# PI_CON.net
KiCad netlist of a schematic drawn in Altium Designer
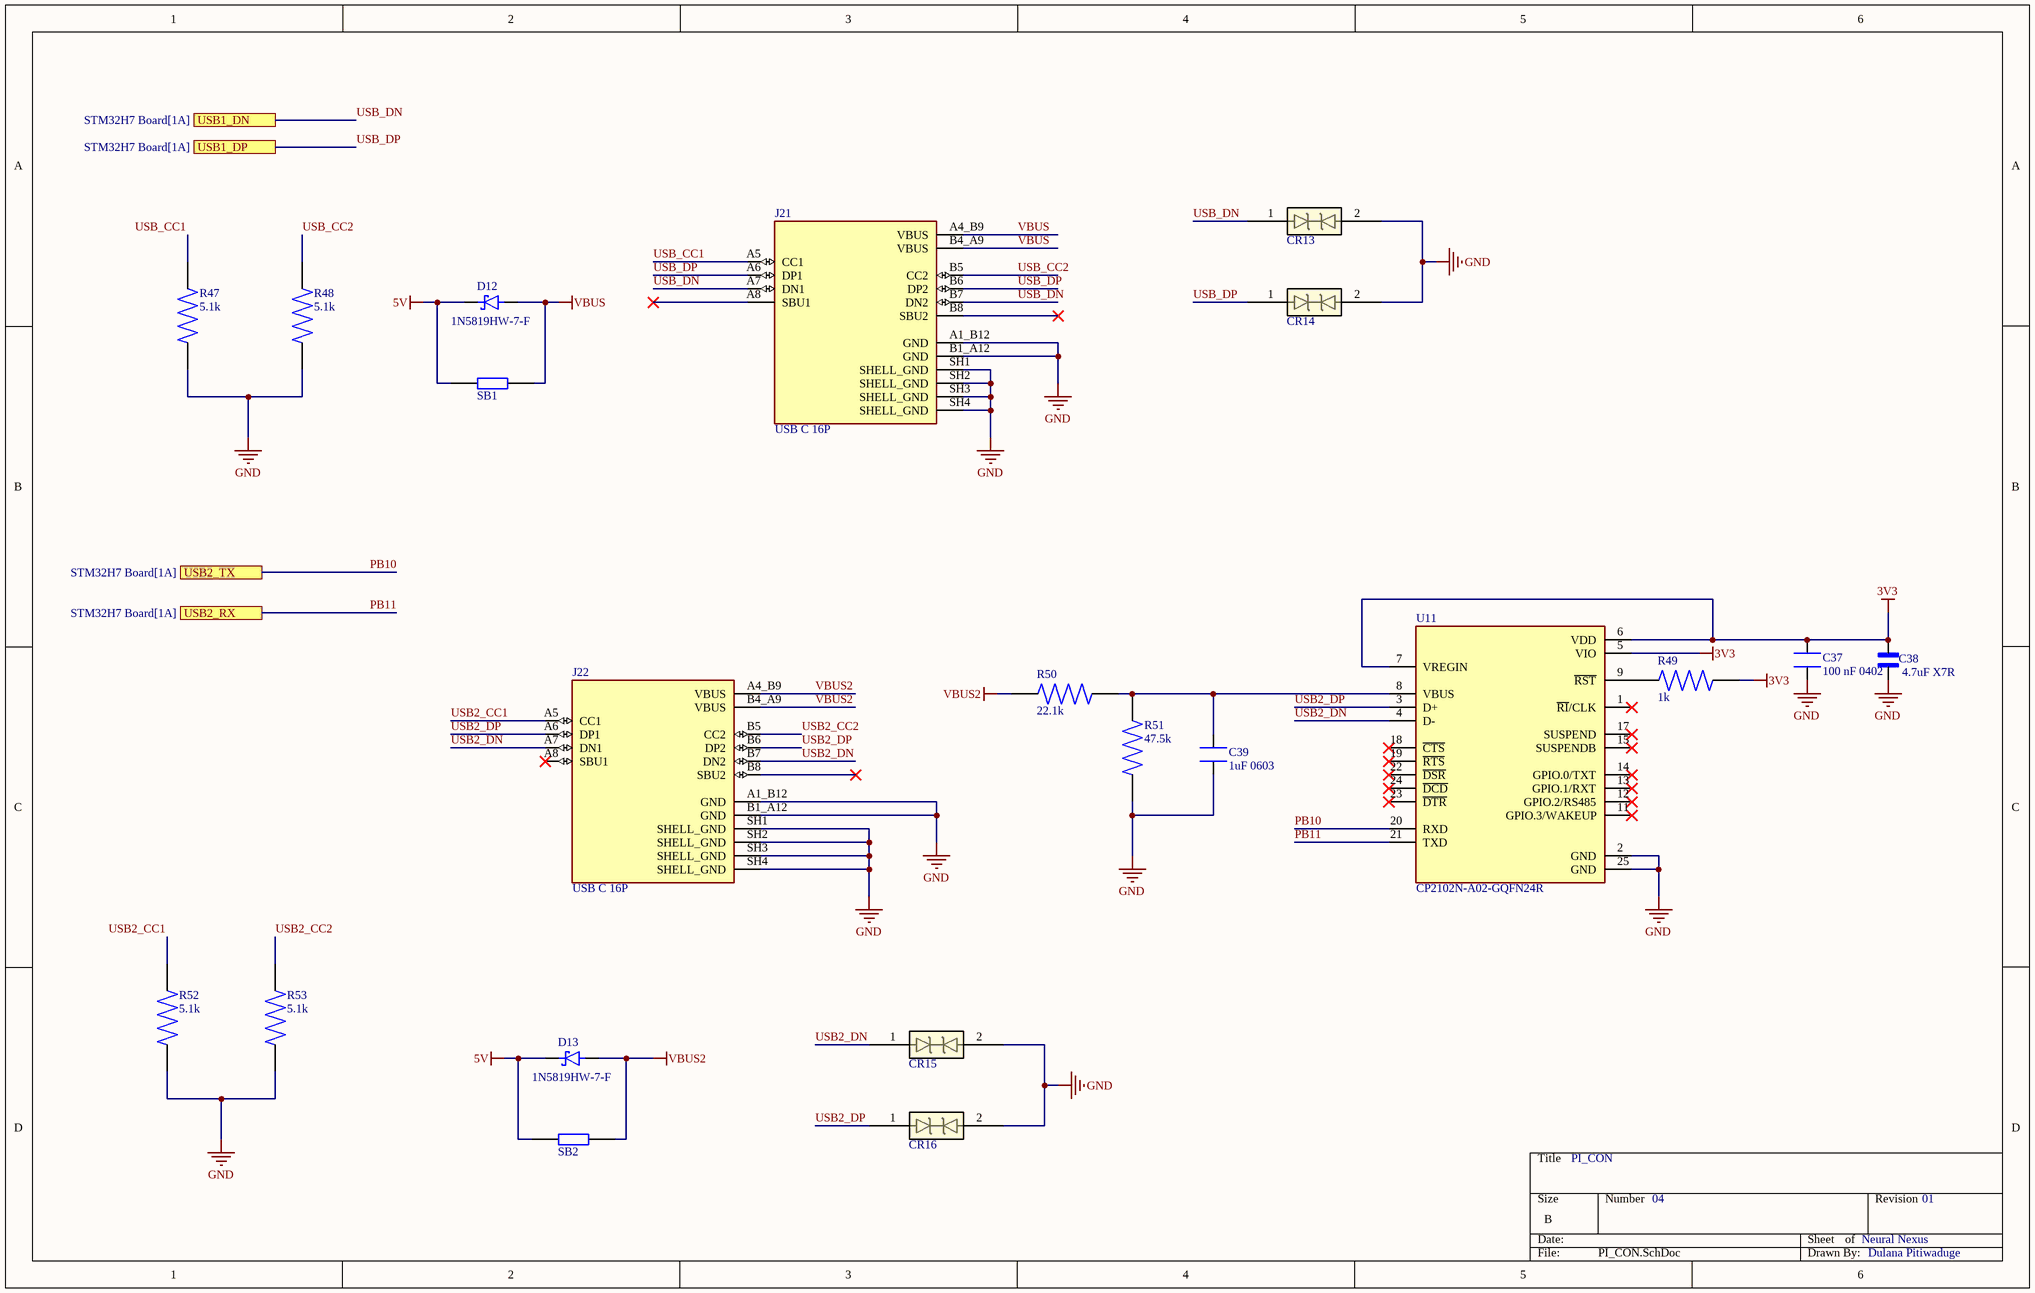
[diagram p0: PI_CON.SchDoc]

(export (version "E")
  (design (tool "Eeschema 10.0.6"))
  (components
    (comp (ref "C37")
      (value "100 nF 0402")
      (footprint "CAPC1005X55N")
      (description "0.1 ÂµF Â±10% 10V Ceramic Capacitor X7R 0402 (1005 Metric)")
      (fields (field (name "MF") "Samsung Electro-Mechanics") (field (name "MP") "CL05B104KP5NNNC"))
      (libsource (lib "EDR") (part "CL05B104KP5NNNC"))
    )
    (comp (ref "C38")
      (value "4.7uF X7R")
      (footprint "CAPC2012X145N")
      (description "C Series 0805 4.7 uF 10 V Â±10% Tolerance X7R SMT Multilayer Ceramic Capacitor")
      (fields (field (name "MF") "TDK") (field (name "MP") "C2012X7R1A475K125AC"))
      (libsource (lib "EDR") (part "C2012X7R1A475K125AC"))
    )
    (comp (ref "C39")
      (value "1uF 0603")
      (footprint "CAPC1608X90")
      (description "1 ÂµF -20%, +80% 16V Ceramic Capacitor Y5V (F) 0603 (1608 Metric)")
      (fields (field (name "MF") "Yageo") (field (name "MP") "CC0603ZRY5V7BB105"))
      (libsource (lib "EDR") (part "CC0603ZRY5V7BB105"))
    )
    (comp (ref "CR13")
      (value "SP0402B-ULC-01ETG")
      (footprint "SP0402_LTF")
      (description "Description")
      (fields (field (name "COPYRIGHT") "Copyright (C) 2025 Ultra Librarian. All rights reserved."))
      (libsource (lib "Schlib1") (part "SP0402B-ULC-01ETG"))
    )
    (comp (ref "CR14")
      (value "SP0402B-ULC-01ETG")
      (footprint "SP0402_LTF")
      (description "Description")
      (fields (field (name "COPYRIGHT") "Copyright (C) 2025 Ultra Librarian. All rights reserved."))
      (libsource (lib "Schlib1") (part "SP0402B-ULC-01ETG"))
    )
    (comp (ref "CR15")
      (value "SP0402B-ULC-01ETG")
      (footprint "SP0402_LTF")
      (description "Description")
      (fields (field (name "COPYRIGHT") "Copyright (C) 2025 Ultra Librarian. All rights reserved."))
      (libsource (lib "Schlib1") (part "SP0402B-ULC-01ETG"))
    )
    (comp (ref "CR16")
      (value "SP0402B-ULC-01ETG")
      (footprint "SP0402_LTF")
      (description "Description")
      (fields (field (name "COPYRIGHT") "Copyright (C) 2025 Ultra Librarian. All rights reserved."))
      (libsource (lib "Schlib1") (part "SP0402B-ULC-01ETG"))
    )
    (comp (ref "D12")
      (value "1N5819HW-7-F")
      (footprint "SOD3715X145N")
      (description "Diode Schottky 40 V 1A Surface Mount SOD-123")
      (fields (field (name "MF") "Diodes Inc."))
      (libsource (lib "Schlib1") (part "1N5819HW-7-F"))
    )
    (comp (ref "D13")
      (value "1N5819HW-7-F")
      (footprint "SOD3715X145N")
      (description "Diode Schottky 40 V 1A Surface Mount SOD-123")
      (fields (field (name "MF") "Diodes Inc."))
      (libsource (lib "Schlib1") (part "1N5819HW-7-F"))
    )
    (comp (ref "J21")
      (value "USB C 16P")
      (footprint "GCT_USB4105-GF-A")
      (description "CONN RCP USB2.0 TYP C 16P SMD RA")
      (fields (field (name "MF") "{'manufacturer': u'GCT'}") (field (name "MP") "USB4105-GF-A"))
      (libsource (lib "Schlib1") (part "USB4105-GF-A"))
    )
    (comp (ref "J22")
      (value "USB C 16P")
      (footprint "GCT_USB4105-GF-A")
      (description "CONN RCP USB2.0 TYP C 16P SMD RA")
      (fields (field (name "MF") "{'manufacturer': u'GCT'}") (field (name "MP") "USB4105-GF-A"))
      (libsource (lib "EDR") (part "USB4105-GF-A"))
    )
    (comp (ref "R47")
      (value "5.1k")
      (footprint "RESC1005X35N")
      (description "5.1 kOhms Â±1% 0.063W, 1/16W Chip Resistor 0402 (1005 Metric) Automotive AEC-Q200 Thick Film")
      (fields (field (name "MF") "Stackpole Electronics Inc") (field (name "MP") "RMCF0402FT5K10"))
      (libsource (lib "Schlib1") (part "RMCF0402FT5K10"))
    )
    (comp (ref "R48")
      (value "5.1k")
      (footprint "RESC1005X35N")
      (description "5.1 kOhms Â±1% 0.063W, 1/16W Chip Resistor 0402 (1005 Metric) Automotive AEC-Q200 Thick Film")
      (fields (field (name "MF") "Stackpole Electronics Inc") (field (name "MP") "RMCF0402FT5K10"))
      (libsource (lib "Schlib1") (part "RMCF0402FT5K10"))
    )
    (comp (ref "R49")
      (value "1k")
      (footprint "RESC1005X40N")
      (description "1 kOhms Â±1% 0.063W, 1/16W Chip Resistor 0402 (1005 Metric) Moisture Resistant Thick Film")
      (fields (field (name "MF") "Yageo Corporation") (field (name "MP") "RC0402FR071KL"))
      (libsource (lib "EDR") (part "RC0402FR-071KL"))
    )
    (comp (ref "R50")
      (value "22.1k")
      (footprint "RESC1508X55N")
      (description "22.1 kOhms Â±1% 0.1W, 1/10W Chip Resistor 0603 (1608 Metric) Automotive AEC-Q200 Thick Film")
      (fields (field (name "MF") "Stackpole Electronics Inc") (field (name "MP") "RMCF0603FT22K1"))
      (libsource (lib "EDR") (part "RMCF0603FT22K1"))
    )
    (comp (ref "R51")
      (value "47.5k")
      (footprint "RESC1005X40N")
      (description "47.5 kOhms Â±1% 0.063W, 1/16W Chip Resistor 0402 (1005 Metric) Moisture Resistant Thick Film")
      (fields (field (name "MF") "Yageo") (field (name "MP") "RC0402FR-0747K5L"))
      (libsource (lib "EDR") (part "RC0402FR-0747K5L"))
    )
    (comp (ref "R52")
      (value "5.1k")
      (footprint "RESC1005X35N")
      (description "5.1 kOhms Â±1% 0.063W, 1/16W Chip Resistor 0402 (1005 Metric) Automotive AEC-Q200 Thick Film")
      (fields (field (name "MF") "Stackpole Electronics Inc") (field (name "MP") "RMCF0402FT5K10"))
      (libsource (lib "Schlib1") (part "RMCF0402FT5K10"))
    )
    (comp (ref "R53")
      (value "5.1k")
      (footprint "RESC1005X35N")
      (description "5.1 kOhms Â±1% 0.063W, 1/16W Chip Resistor 0402 (1005 Metric) Automotive AEC-Q200 Thick Film")
      (fields (field (name "MF") "Stackpole Electronics Inc") (field (name "MP") "RMCF0402FT5K10"))
      (libsource (lib "Schlib1") (part "RMCF0402FT5K10"))
    )
    (comp (ref "SB1")
      (value "0R")
      (footprint "RESC1608X55N")
      (description "Resistor, AS 0603 0R Jumper 100mW, AEC-Q, Anti-Sulur ¦ Bourns CR0603AJ/-000EAS")
      (fields (field (name "MF") "Bourns Inc.") (field (name "MP") "CR0603AJ/-000EAS"))
      (libsource (lib "Schlib1") (part "CR0603AJ/-000EAS"))
    )
    (comp (ref "SB2")
      (value "0R")
      (footprint "RESC1608X55N")
      (description "Resistor, AS 0603 0R Jumper 100mW, AEC-Q, Anti-Sulur ¦ Bourns CR0603AJ/-000EAS")
      (fields (field (name "MF") "Bourns Inc.") (field (name "MP") "CR0603AJ/-000EAS"))
      (libsource (lib "Schlib1") (part "CR0603AJ/-000EAS"))
    )
    (comp (ref "U11")
      (value "CP2102N-A02-GQFN24R")
      (footprint "EDR:QFN50P400X400X80-25N")
      (description "IC USB TO UART BRIDGE QFN24")
      (libsource (lib "EDR") (part "CP2102N-A02-GQFN24R"))
    )
  )
  (nets
    (net (code "1") (name "/PB10") (class "Default")
      (node (ref "U11") (pin "20") (pinfunction "RXD_20") (pintype "passive"))
    )
    (net (code "2") (name "/PB11") (class "Default")
      (node (ref "U11") (pin "21") (pinfunction "TXD_21") (pintype "passive"))
    )
    (net (code "3") (name "/USB2_CC1") (class "Default")
      (node (ref "J22") (pin "A5") (pinfunction "CC1_A5") (pintype "bidirectional"))
      (node (ref "R52") (pin "1") (pinfunction "1_1") (pintype "passive"))
    )
    (net (code "4") (name "/USB2_CC2") (class "Default")
      (node (ref "J22") (pin "B5") (pinfunction "CC2_B5") (pintype "bidirectional"))
      (node (ref "R53") (pin "1") (pinfunction "1_1") (pintype "passive"))
    )
    (net (code "5") (name "/USB2_DN") (class "Default")
      (node (ref "CR15") (pin "1") (pinfunction "1_1") (pintype "passive"))
      (node (ref "J22") (pin "A7") (pinfunction "DN1_A7") (pintype "bidirectional"))
      (node (ref "J22") (pin "B7") (pinfunction "DN2_B7") (pintype "bidirectional"))
      (node (ref "U11") (pin "4") (pinfunction "D-_4") (pintype "passive"))
    )
    (net (code "6") (name "/USB2_DP") (class "Default")
      (node (ref "CR16") (pin "1") (pinfunction "1_1") (pintype "passive"))
      (node (ref "J22") (pin "A6") (pinfunction "DP1_A6") (pintype "bidirectional"))
      (node (ref "J22") (pin "B6") (pinfunction "DP2_B6") (pintype "bidirectional"))
      (node (ref "U11") (pin "3") (pinfunction "D+_3") (pintype "passive"))
    )
    (net (code "7") (name "/USB_CC1") (class "Default")
      (node (ref "J21") (pin "A5") (pinfunction "CC1_A5") (pintype "bidirectional"))
      (node (ref "R47") (pin "1") (pinfunction "1_1") (pintype "passive"))
    )
    (net (code "8") (name "/USB_CC2") (class "Default")
      (node (ref "J21") (pin "B5") (pinfunction "CC2_B5") (pintype "bidirectional"))
      (node (ref "R48") (pin "1") (pinfunction "1_1") (pintype "passive"))
    )
    (net (code "9") (name "/USB_DN") (class "Default")
      (node (ref "CR13") (pin "1") (pinfunction "1_1") (pintype "passive"))
      (node (ref "J21") (pin "A7") (pinfunction "DN1_A7") (pintype "bidirectional"))
      (node (ref "J21") (pin "B7") (pinfunction "DN2_B7") (pintype "bidirectional"))
    )
    (net (code "10") (name "/USB_DP") (class "Default")
      (node (ref "CR14") (pin "1") (pinfunction "1_1") (pintype "passive"))
      (node (ref "J21") (pin "A6") (pinfunction "DP1_A6") (pintype "bidirectional"))
      (node (ref "J21") (pin "B6") (pinfunction "DP2_B6") (pintype "bidirectional"))
    )
    (net (code "11") (name "3V3") (class "Default")
      (node (ref "C37") (pin "2") (pinfunction "2_2") (pintype "passive"))
      (node (ref "C38") (pin "2") (pinfunction "2_2") (pintype "passive"))
      (node (ref "R49") (pin "2") (pinfunction "2_2") (pintype "passive"))
      (node (ref "U11") (pin "5") (pinfunction "VIO_5") (pintype "power_in"))
      (node (ref "U11") (pin "6") (pinfunction "VDD_6") (pintype "power_in"))
      (node (ref "U11") (pin "7") (pinfunction "VREGIN_7") (pintype "passive"))
    )
    (net (code "12") (name "5V") (class "Default")
      (node (ref "D12") (pin "C") (pinfunction "K_C") (pintype "passive"))
      (node (ref "D13") (pin "C") (pinfunction "K_C") (pintype "passive"))
      (node (ref "SB1") (pin "1") (pinfunction "1_1") (pintype "passive"))
      (node (ref "SB2") (pin "1") (pinfunction "1_1") (pintype "passive"))
    )
    (net (code "13") (name "GND") (class "Default")
      (node (ref "C37") (pin "1") (pinfunction "1_1") (pintype "passive"))
      (node (ref "C38") (pin "1") (pinfunction "1_1") (pintype "passive"))
      (node (ref "C39") (pin "2") (pinfunction "2_2") (pintype "passive"))
      (node (ref "CR13") (pin "2") (pinfunction "2_2") (pintype "passive"))
      (node (ref "CR14") (pin "2") (pinfunction "2_2") (pintype "passive"))
      (node (ref "CR15") (pin "2") (pinfunction "2_2") (pintype "passive"))
      (node (ref "CR16") (pin "2") (pinfunction "2_2") (pintype "passive"))
      (node (ref "J21") (pin "A1_B12") (pinfunction "GND_A1_B12") (pintype "power_in"))
      (node (ref "J21") (pin "B1_A12") (pinfunction "GND_B1_A12") (pintype "power_in"))
      (node (ref "J21") (pin "SH1") (pinfunction "SHELL_GND_SH1") (pintype "power_in"))
      (node (ref "J21") (pin "SH2") (pinfunction "SHELL_GND_SH2") (pintype "power_in"))
      (node (ref "J21") (pin "SH3") (pinfunction "SHELL_GND_SH3") (pintype "power_in"))
      (node (ref "J21") (pin "SH4") (pinfunction "SHELL_GND_SH4") (pintype "power_in"))
      (node (ref "J22") (pin "A1_B12") (pinfunction "GND_A1_B12") (pintype "power_in"))
      (node (ref "J22") (pin "B1_A12") (pinfunction "GND_B1_A12") (pintype "power_in"))
      (node (ref "J22") (pin "SH1") (pinfunction "SHELL_GND_SH1") (pintype "power_in"))
      (node (ref "J22") (pin "SH2") (pinfunction "SHELL_GND_SH2") (pintype "power_in"))
      (node (ref "J22") (pin "SH3") (pinfunction "SHELL_GND_SH3") (pintype "power_in"))
      (node (ref "J22") (pin "SH4") (pinfunction "SHELL_GND_SH4") (pintype "power_in"))
      (node (ref "R47") (pin "2") (pinfunction "2_2") (pintype "passive"))
      (node (ref "R48") (pin "2") (pinfunction "2_2") (pintype "passive"))
      (node (ref "R51") (pin "1") (pinfunction "1_1") (pintype "passive"))
      (node (ref "R52") (pin "2") (pinfunction "2_2") (pintype "passive"))
      (node (ref "R53") (pin "2") (pinfunction "2_2") (pintype "passive"))
      (node (ref "U11") (pin "2") (pinfunction "GND_2") (pintype "power_in"))
      (node (ref "U11") (pin "25") (pinfunction "GND_25") (pintype "power_in"))
    )
    (net (code "14") (name "Net-(U11-VBUS)") (class "Default")
      (node (ref "C39") (pin "1") (pinfunction "1_1") (pintype "passive"))
      (node (ref "R50") (pin "2") (pinfunction "2_2") (pintype "passive"))
      (node (ref "R51") (pin "2") (pinfunction "2_2") (pintype "passive"))
      (node (ref "U11") (pin "8") (pinfunction "VBUS_8") (pintype "passive"))
    )
    (net (code "15") (name "Net-(U11-~{RST})") (class "Default")
      (node (ref "R49") (pin "1") (pinfunction "1_1") (pintype "passive"))
      (node (ref "U11") (pin "9") (pinfunction "~{RST}_9") (pintype "passive"))
    )
    (net (code "16") (name "VBUS") (class "Default")
      (node (ref "D12") (pin "A") (pinfunction "A_A") (pintype "passive"))
      (node (ref "J21") (pin "A4_B9") (pinfunction "VBUS_A4_B9") (pintype "power_in"))
      (node (ref "J21") (pin "B4_A9") (pinfunction "VBUS_B4_A9") (pintype "power_in"))
      (node (ref "SB1") (pin "2") (pinfunction "2_2") (pintype "passive"))
    )
    (net (code "17") (name "VBUS2") (class "Default")
      (node (ref "D13") (pin "A") (pinfunction "A_A") (pintype "passive"))
      (node (ref "J22") (pin "A4_B9") (pinfunction "VBUS_A4_B9") (pintype "power_in"))
      (node (ref "J22") (pin "B4_A9") (pinfunction "VBUS_B4_A9") (pintype "power_in"))
      (node (ref "R50") (pin "1") (pinfunction "1_1") (pintype "passive"))
      (node (ref "SB2") (pin "2") (pinfunction "2_2") (pintype "passive"))
    )
    (net (code "18") (name "unconnected-(J21-SBU1-PadA8)") (class "Default")
      (node (ref "J21") (pin "A8") (pinfunction "SBU1_A8") (pintype "passive+no_connect"))
    )
    (net (code "19") (name "unconnected-(J21-SBU2-PadB8)") (class "Default")
      (node (ref "J21") (pin "B8") (pinfunction "SBU2_B8") (pintype "passive+no_connect"))
    )
    (net (code "20") (name "unconnected-(J22-SBU1-PadA8)") (class "Default")
      (node (ref "J22") (pin "A8") (pinfunction "SBU1_A8") (pintype "bidirectional+no_connect"))
    )
    (net (code "21") (name "unconnected-(J22-SBU2-PadB8)") (class "Default")
      (node (ref "J22") (pin "B8") (pinfunction "SBU2_B8") (pintype "bidirectional+no_connect"))
    )
    (net (code "22") (name "unconnected-(U11-GPIO.0{slash}TXT-Pad14)") (class "Default")
      (node (ref "U11") (pin "14") (pinfunction "GPIO.0/TXT_14") (pintype "passive+no_connect"))
    )
    (net (code "23") (name "unconnected-(U11-GPIO.1{slash}RXT-Pad13)") (class "Default")
      (node (ref "U11") (pin "13") (pinfunction "GPIO.1/RXT_13") (pintype "passive+no_connect"))
    )
    (net (code "24") (name "unconnected-(U11-GPIO.2{slash}RS485-Pad12)") (class "Default")
      (node (ref "U11") (pin "12") (pinfunction "GPIO.2/RS485_12") (pintype "passive+no_connect"))
    )
    (net (code "25") (name "unconnected-(U11-GPIO.3{slash}WAKEUP-Pad11)") (class "Default")
      (node (ref "U11") (pin "11") (pinfunction "GPIO.3/WAKEUP_11") (pintype "passive+no_connect"))
    )
    (net (code "26") (name "unconnected-(U11-SUSPEND-Pad17)") (class "Default")
      (node (ref "U11") (pin "17") (pinfunction "SUSPEND_17") (pintype "passive+no_connect"))
    )
    (net (code "27") (name "unconnected-(U11-SUSPENDB-Pad15)") (class "Default")
      (node (ref "U11") (pin "15") (pinfunction "SUSPENDB_15") (pintype "passive+no_connect"))
    )
    (net (code "28") (name "unconnected-(U11-~{CTS}-Pad18)") (class "Default")
      (node (ref "U11") (pin "18") (pinfunction "~{CTS}_18") (pintype "passive+no_connect"))
    )
    (net (code "29") (name "unconnected-(U11-~{DCD}-Pad24)") (class "Default")
      (node (ref "U11") (pin "24") (pinfunction "~{DCD}_24") (pintype "passive+no_connect"))
    )
    (net (code "30") (name "unconnected-(U11-~{DSR}-Pad22)") (class "Default")
      (node (ref "U11") (pin "22") (pinfunction "~{DSR}_22") (pintype "passive+no_connect"))
    )
    (net (code "31") (name "unconnected-(U11-~{DTR}-Pad23)") (class "Default")
      (node (ref "U11") (pin "23") (pinfunction "~{DTR}_23") (pintype "passive+no_connect"))
    )
    (net (code "32") (name "unconnected-(U11-~{RI}{slash}CLK-Pad1)") (class "Default")
      (node (ref "U11") (pin "1") (pinfunction "~{RI}/CLK_1") (pintype "passive+no_connect"))
    )
    (net (code "33") (name "unconnected-(U11-~{RTS}-Pad19)") (class "Default")
      (node (ref "U11") (pin "19") (pinfunction "~{RTS}_19") (pintype "passive+no_connect"))
    )
  )
)
